# Sheet2.net
KiCad netlist of a schematic drawn in Altium Designer
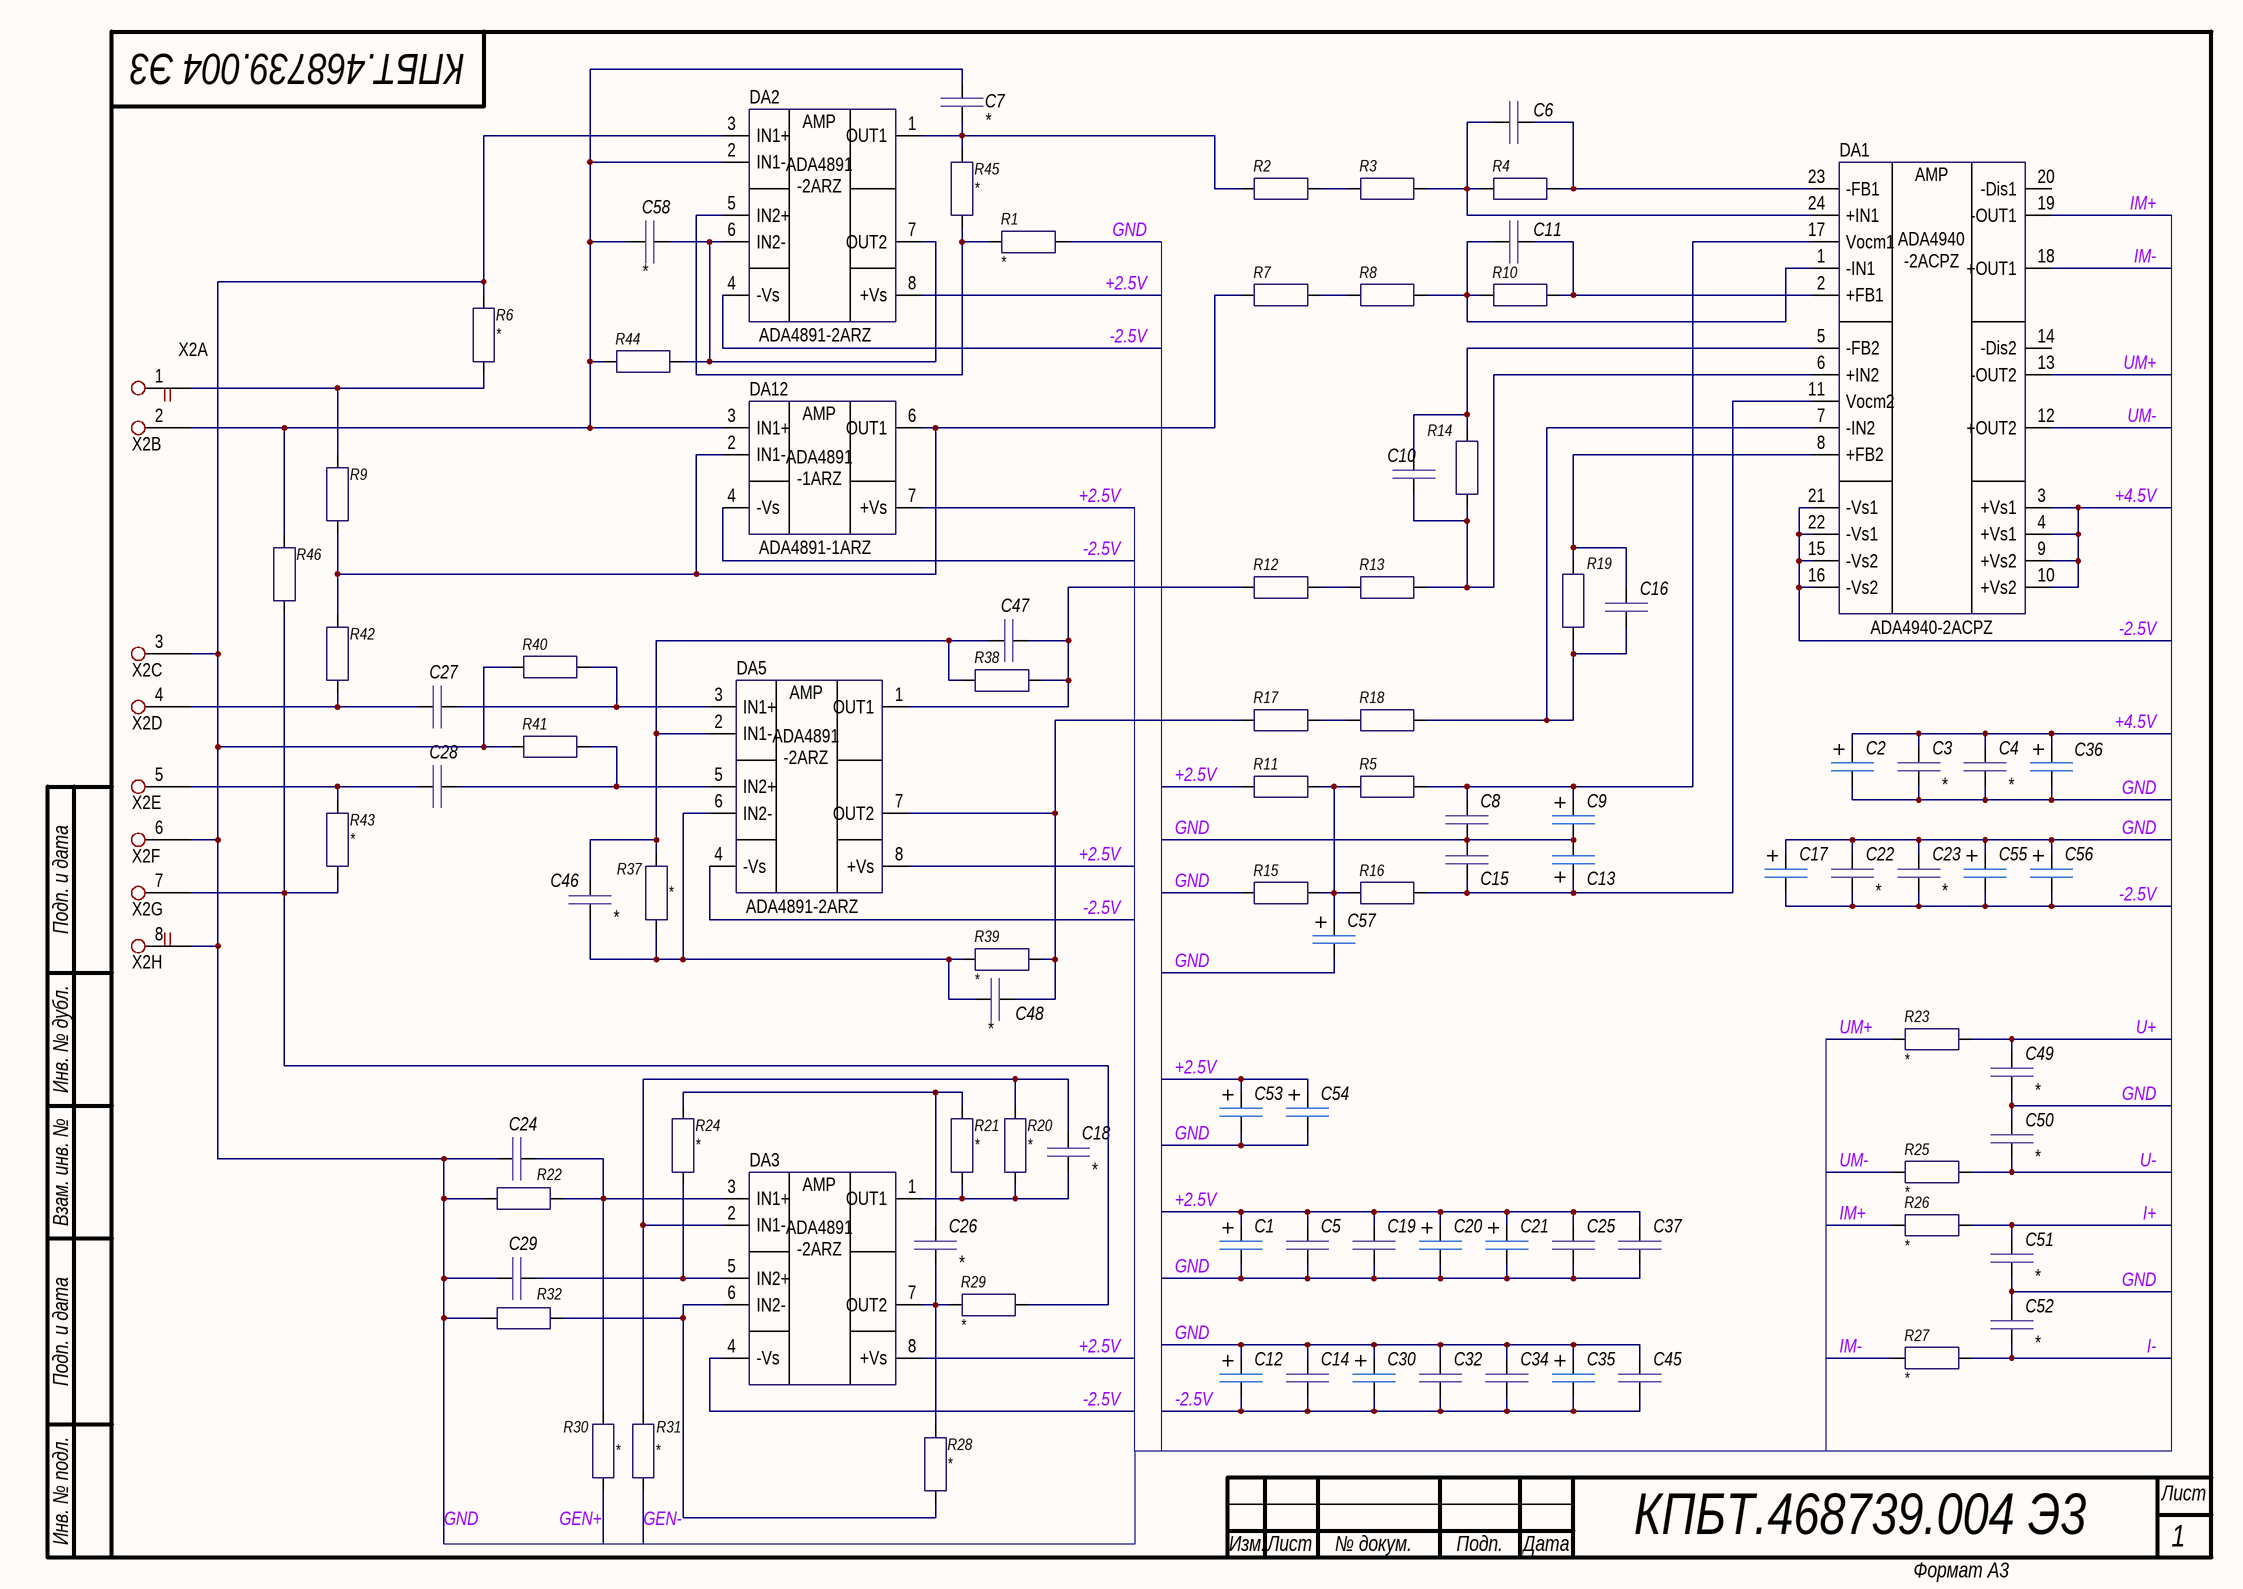
[diagram p0: Sheet2.SchDoc]

(export (version "E")
  (design (tool "Eeschema 10.0.6"))
  (components
    (comp (ref "C1")
      (value "~")
      (footprint "CAPT: tepy B")
      (fields (field (name "PART NUMBER") "CAPT: tepy B"))
      (libsource (lib "LibDb") (part "CAPT{colon} tepy B"))
    )
    (comp (ref "C2")
      (value "~")
      (footprint "CAPT: tepy B")
      (fields (field (name "PART NUMBER") "CAPT: tepy B"))
      (libsource (lib "LibDb") (part "CAPT{colon} tepy B"))
    )
    (comp (ref "C3")
      (value "*")
      (footprint "CAP:0805")
      (fields (field (name "PART NUMBER") "Capacitor 0805"))
      (libsource (lib "LibDb") (part "CAP{colon}0805"))
    )
    (comp (ref "C4")
      (value "*")
      (footprint "CAP:0805")
      (fields (field (name "PART NUMBER") "Capacitor 0805"))
      (libsource (lib "LibDb") (part "CAP{colon}0805"))
    )
    (comp (ref "C5")
      (value "*")
      (footprint "CAP:0805")
      (fields (field (name "PART NUMBER") "Capacitor 0805"))
      (libsource (lib "LibDb") (part "CAP{colon}0805"))
    )
    (comp (ref "C6")
      (value "*")
      (footprint "CAP:0805")
      (fields (field (name "PART NUMBER") "Capacitor 0805"))
      (libsource (lib "LibDb") (part "CAP{colon}0805"))
    )
    (comp (ref "C7")
      (value "*")
      (footprint "CAP:0805")
      (fields (field (name "PART NUMBER") "Capacitor 0805"))
      (libsource (lib "LibDb") (part "CAP{colon}0805"))
    )
    (comp (ref "C8")
      (value "*")
      (footprint "CAP:0805")
      (fields (field (name "PART NUMBER") "Capacitor 0805"))
      (libsource (lib "LibDb") (part "CAP{colon}0805"))
    )
    (comp (ref "C9")
      (value "~")
      (footprint "CAPT: tepy B")
      (fields (field (name "PART NUMBER") "CAPT: tepy B"))
      (libsource (lib "LibDb") (part "CAPT{colon} tepy B"))
    )
    (comp (ref "C10")
      (value "*")
      (footprint "CAP:0805")
      (fields (field (name "PART NUMBER") "Capacitor 0805"))
      (libsource (lib "LibDb") (part "CAP{colon}0805"))
    )
    (comp (ref "C11")
      (value "*")
      (footprint "CAP:0805")
      (fields (field (name "PART NUMBER") "Capacitor 0805"))
      (libsource (lib "LibDb") (part "CAP{colon}0805"))
    )
    (comp (ref "C12")
      (value "~")
      (footprint "CAPT: tepy B")
      (fields (field (name "PART NUMBER") "CAPT: tepy B"))
      (libsource (lib "LibDb") (part "CAPT{colon} tepy B"))
    )
    (comp (ref "C13")
      (value "~")
      (footprint "CAPT: tepy B")
      (fields (field (name "PART NUMBER") "CAPT: tepy B"))
      (libsource (lib "LibDb") (part "CAPT{colon} tepy B"))
    )
    (comp (ref "C14")
      (value "*")
      (footprint "CAP:0805")
      (fields (field (name "PART NUMBER") "Capacitor 0805"))
      (libsource (lib "LibDb") (part "CAP{colon}0805"))
    )
    (comp (ref "C15")
      (value "*")
      (footprint "CAP:0805")
      (fields (field (name "PART NUMBER") "Capacitor 0805"))
      (libsource (lib "LibDb") (part "CAP{colon}0805"))
    )
    (comp (ref "C16")
      (value "*")
      (footprint "CAP:0805")
      (fields (field (name "PART NUMBER") "Capacitor 0805"))
      (libsource (lib "LibDb") (part "CAP{colon}0805"))
    )
    (comp (ref "C17")
      (value "~")
      (footprint "CAPT: tepy B")
      (fields (field (name "PART NUMBER") "CAPT: tepy B"))
      (libsource (lib "LibDb") (part "CAPT{colon} tepy B"))
    )
    (comp (ref "C18")
      (value "*")
      (footprint "CAP:0805")
      (fields (field (name "PART NUMBER") "Capacitor 0805"))
      (libsource (lib "LibDb") (part "CAP{colon}0805"))
    )
    (comp (ref "C19")
      (value "*")
      (footprint "CAP:0805")
      (fields (field (name "PART NUMBER") "Capacitor 0805"))
      (libsource (lib "LibDb") (part "CAP{colon}0805"))
    )
    (comp (ref "C20")
      (value "~")
      (footprint "CAPT: tepy B")
      (fields (field (name "PART NUMBER") "CAPT: tepy B"))
      (libsource (lib "LibDb") (part "CAPT{colon} tepy B"))
    )
    (comp (ref "C21")
      (value "~")
      (footprint "CAPT: tepy B")
      (fields (field (name "PART NUMBER") "CAPT: tepy B"))
      (libsource (lib "LibDb") (part "CAPT{colon} tepy B"))
    )
    (comp (ref "C22")
      (value "*")
      (footprint "CAP:0805")
      (fields (field (name "PART NUMBER") "Capacitor 0805"))
      (libsource (lib "LibDb") (part "CAP{colon}0805"))
    )
    (comp (ref "C23")
      (value "*")
      (footprint "CAP:0805")
      (fields (field (name "PART NUMBER") "Capacitor 0805"))
      (libsource (lib "LibDb") (part "CAP{colon}0805"))
    )
    (comp (ref "C24")
      (value "*")
      (footprint "CAP:0805")
      (fields (field (name "PART NUMBER") "Capacitor 0805"))
      (libsource (lib "LibDb") (part "CAP{colon}0805"))
    )
    (comp (ref "C25")
      (value "*")
      (footprint "CAP:0805")
      (fields (field (name "PART NUMBER") "Capacitor 0805"))
      (libsource (lib "LibDb") (part "CAP{colon}0805"))
    )
    (comp (ref "C26")
      (value "*")
      (footprint "CAP:0805")
      (fields (field (name "PART NUMBER") "Capacitor 0805"))
      (libsource (lib "LibDb") (part "CAP{colon}0805"))
    )
    (comp (ref "C27")
      (value "*")
      (footprint "CAP:0805")
      (fields (field (name "PART NUMBER") "Capacitor 0805"))
      (libsource (lib "LibDb") (part "CAP{colon}0805"))
    )
    (comp (ref "C28")
      (value "*")
      (footprint "CAP:0805")
      (fields (field (name "PART NUMBER") "Capacitor 0805"))
      (libsource (lib "LibDb") (part "CAP{colon}0805"))
    )
    (comp (ref "C29")
      (value "*")
      (footprint "CAP:0805")
      (fields (field (name "PART NUMBER") "Capacitor 0805"))
      (libsource (lib "LibDb") (part "CAP{colon}0805"))
    )
    (comp (ref "C30")
      (value "~")
      (footprint "CAPT: tepy B")
      (fields (field (name "PART NUMBER") "CAPT: tepy B"))
      (libsource (lib "LibDb") (part "CAPT{colon} tepy B"))
    )
    (comp (ref "C32")
      (value "*")
      (footprint "CAP:0805")
      (fields (field (name "PART NUMBER") "Capacitor 0805"))
      (libsource (lib "LibDb") (part "CAP{colon}0805"))
    )
    (comp (ref "C34")
      (value "*")
      (footprint "CAP:0805")
      (fields (field (name "PART NUMBER") "Capacitor 0805"))
      (libsource (lib "LibDb") (part "CAP{colon}0805"))
    )
    (comp (ref "C35")
      (value "~")
      (footprint "CAPT: tepy B")
      (fields (field (name "PART NUMBER") "CAPT: tepy B"))
      (libsource (lib "LibDb") (part "CAPT{colon} tepy B"))
    )
    (comp (ref "C36")
      (value "~")
      (footprint "CAPT: tepy B")
      (fields (field (name "PART NUMBER") "CAPT: tepy B"))
      (libsource (lib "LibDb") (part "CAPT{colon} tepy B"))
    )
    (comp (ref "C37")
      (value "*")
      (footprint "CAP:0805")
      (fields (field (name "PART NUMBER") "Capacitor 0805"))
      (libsource (lib "LibDb") (part "CAP{colon}0805"))
    )
    (comp (ref "C45")
      (value "*")
      (footprint "CAP:0805")
      (fields (field (name "PART NUMBER") "Capacitor 0805"))
      (libsource (lib "LibDb") (part "CAP{colon}0805"))
    )
    (comp (ref "C46")
      (value "*")
      (footprint "CAP:0805")
      (fields (field (name "PART NUMBER") "Capacitor 0805"))
      (libsource (lib "LibDb") (part "CAP{colon}0805"))
    )
    (comp (ref "C47")
      (value "*")
      (footprint "CAP:0805")
      (fields (field (name "PART NUMBER") "Capacitor 0805"))
      (libsource (lib "LibDb") (part "CAP{colon}0805"))
    )
    (comp (ref "C48")
      (value "*")
      (footprint "CAP:0805")
      (fields (field (name "PART NUMBER") "Capacitor 0805"))
      (libsource (lib "LibDb") (part "CAP{colon}0805"))
    )
    (comp (ref "C49")
      (value "*")
      (footprint "CAP:0805")
      (fields (field (name "PART NUMBER") "Capacitor 0805"))
      (libsource (lib "LibDb") (part "CAP{colon}0805"))
    )
    (comp (ref "C50")
      (value "*")
      (footprint "CAP:0805")
      (fields (field (name "PART NUMBER") "Capacitor 0805"))
      (libsource (lib "LibDb") (part "CAP{colon}0805"))
    )
    (comp (ref "C51")
      (value "*")
      (footprint "CAP:0805")
      (fields (field (name "PART NUMBER") "Capacitor 0805"))
      (libsource (lib "LibDb") (part "CAP{colon}0805"))
    )
    (comp (ref "C52")
      (value "*")
      (footprint "CAP:0805")
      (fields (field (name "PART NUMBER") "Capacitor 0805"))
      (libsource (lib "LibDb") (part "CAP{colon}0805"))
    )
    (comp (ref "C53")
      (value "~")
      (footprint "CAPT: tepy B")
      (fields (field (name "PART NUMBER") "CAPT: tepy B"))
      (libsource (lib "LibDb") (part "CAPT{colon} tepy B"))
    )
    (comp (ref "C54")
      (value "~")
      (footprint "CAPT: tepy B")
      (fields (field (name "PART NUMBER") "CAPT: tepy B"))
      (libsource (lib "LibDb") (part "CAPT{colon} tepy B"))
    )
    (comp (ref "C55")
      (value "~")
      (footprint "CAPT: tepy B")
      (fields (field (name "PART NUMBER") "CAPT: tepy B"))
      (libsource (lib "LibDb") (part "CAPT{colon} tepy B"))
    )
    (comp (ref "C56")
      (value "~")
      (footprint "CAPT: tepy B")
      (fields (field (name "PART NUMBER") "CAPT: tepy B"))
      (libsource (lib "LibDb") (part "CAPT{colon} tepy B"))
    )
    (comp (ref "C57")
      (value "~")
      (footprint "CAPT: tepy B")
      (fields (field (name "PART NUMBER") "CAPT: tepy B"))
      (libsource (lib "LibDb") (part "CAPT{colon} tepy B"))
    )
    (comp (ref "C58")
      (value "*")
      (footprint "CAP:0805")
      (fields (field (name "PART NUMBER") "Capacitor 0805"))
      (libsource (lib "LibDb") (part "CAP{colon}0805"))
    )
    (comp (ref "DA1")
      (value "ADA4940-2ACPZ")
      (footprint "LFCSP-24")
      (libsource (lib "LibDb") (part "ADA4940-2ACPZ"))
    )
    (comp (ref "DA2")
      (value "ADA4891-2ARZ")
      (footprint "SOIC-8")
      (libsource (lib "LibDb") (part "ADA4891-2ARZ"))
    )
    (comp (ref "DA3")
      (value "ADA4891-2ARZ")
      (footprint "SOIC-8")
      (libsource (lib "LibDb") (part "ADA4891-2ARZ"))
    )
    (comp (ref "DA5")
      (value "ADA4891-2ARZ")
      (footprint "SOIC-8")
      (libsource (lib "LibDb") (part "ADA4891-2ARZ"))
    )
    (comp (ref "DA12")
      (value "ADA4891-1ARZ")
      (footprint "SOIC-8")
      (libsource (lib "LibDb") (part "ADA4891-1ARZ"))
    )
    (comp (ref "R1")
      (value "*")
      (footprint "RES:0805")
      (fields (field (name "PART NUMBER") "Resistor 0805"))
      (libsource (lib "LibDb") (part "RES{colon}0805"))
    )
    (comp (ref "R2")
      (value "*")
      (footprint "RES:0805")
      (fields (field (name "PART NUMBER") "Resistor 0805"))
      (libsource (lib "LibDb") (part "RES{colon}0805"))
    )
    (comp (ref "R3")
      (value "*")
      (footprint "RES:0805")
      (fields (field (name "PART NUMBER") "Resistor 0805"))
      (libsource (lib "LibDb") (part "RES{colon}0805"))
    )
    (comp (ref "R4")
      (value "*")
      (footprint "RES:0805")
      (fields (field (name "PART NUMBER") "Resistor 0805"))
      (libsource (lib "LibDb") (part "RES{colon}0805"))
    )
    (comp (ref "R5")
      (value "*")
      (footprint "RES:0805")
      (fields (field (name "PART NUMBER") "Resistor 0805"))
      (libsource (lib "LibDb") (part "RES{colon}0805"))
    )
    (comp (ref "R6")
      (value "*")
      (footprint "RES:0805")
      (fields (field (name "PART NUMBER") "Resistor 0805"))
      (libsource (lib "LibDb") (part "RES{colon}0805"))
    )
    (comp (ref "R7")
      (value "*")
      (footprint "RES:0805")
      (fields (field (name "PART NUMBER") "Resistor 0805"))
      (libsource (lib "LibDb") (part "RES{colon}0805"))
    )
    (comp (ref "R8")
      (value "*")
      (footprint "RES:0805")
      (fields (field (name "PART NUMBER") "Resistor 0805"))
      (libsource (lib "LibDb") (part "RES{colon}0805"))
    )
    (comp (ref "R9")
      (value "*")
      (footprint "RES:0805")
      (fields (field (name "PART NUMBER") "Resistor 0805"))
      (libsource (lib "LibDb") (part "RES{colon}0805"))
    )
    (comp (ref "R10")
      (value "*")
      (footprint "RES:0805")
      (fields (field (name "PART NUMBER") "Resistor 0805"))
      (libsource (lib "LibDb") (part "RES{colon}0805"))
    )
    (comp (ref "R11")
      (value "*")
      (footprint "RES:0805")
      (fields (field (name "PART NUMBER") "Resistor 0805"))
      (libsource (lib "LibDb") (part "RES{colon}0805"))
    )
    (comp (ref "R12")
      (value "*")
      (footprint "RES:0805")
      (fields (field (name "PART NUMBER") "Resistor 0805"))
      (libsource (lib "LibDb") (part "RES{colon}0805"))
    )
    (comp (ref "R13")
      (value "*")
      (footprint "RES:0805")
      (fields (field (name "PART NUMBER") "Resistor 0805"))
      (libsource (lib "LibDb") (part "RES{colon}0805"))
    )
    (comp (ref "R14")
      (value "*")
      (footprint "RES:0805")
      (fields (field (name "PART NUMBER") "Resistor 0805"))
      (libsource (lib "LibDb") (part "RES{colon}0805"))
    )
    (comp (ref "R15")
      (value "*")
      (footprint "RES:0805")
      (fields (field (name "PART NUMBER") "Resistor 0805"))
      (libsource (lib "LibDb") (part "RES{colon}0805"))
    )
    (comp (ref "R16")
      (value "*")
      (footprint "RES:0805")
      (fields (field (name "PART NUMBER") "Resistor 0805"))
      (libsource (lib "LibDb") (part "RES{colon}0805"))
    )
    (comp (ref "R17")
      (value "*")
      (footprint "RES:0805")
      (fields (field (name "PART NUMBER") "Resistor 0805"))
      (libsource (lib "LibDb") (part "RES{colon}0805"))
    )
    (comp (ref "R18")
      (value "*")
      (footprint "RES:0805")
      (fields (field (name "PART NUMBER") "Resistor 0805"))
      (libsource (lib "LibDb") (part "RES{colon}0805"))
    )
    (comp (ref "R19")
      (value "*")
      (footprint "RES:0805")
      (fields (field (name "PART NUMBER") "Resistor 0805"))
      (libsource (lib "LibDb") (part "RES{colon}0805"))
    )
    (comp (ref "R20")
      (value "*")
      (footprint "RES:0805")
      (fields (field (name "PART NUMBER") "Resistor 0805"))
      (libsource (lib "LibDb") (part "RES{colon}0805"))
    )
    (comp (ref "R21")
      (value "*")
      (footprint "RES:0805")
      (fields (field (name "PART NUMBER") "Resistor 0805"))
      (libsource (lib "LibDb") (part "RES{colon}0805"))
    )
    (comp (ref "R22")
      (value "*")
      (footprint "RES:0805")
      (fields (field (name "PART NUMBER") "Resistor 0805"))
      (libsource (lib "LibDb") (part "RES{colon}0805"))
    )
    (comp (ref "R23")
      (value "*")
      (footprint "RES:0805")
      (fields (field (name "PART NUMBER") "Resistor 0805"))
      (libsource (lib "LibDb") (part "RES{colon}0805"))
    )
    (comp (ref "R24")
      (value "*")
      (footprint "RES:0805")
      (fields (field (name "PART NUMBER") "Resistor 0805"))
      (libsource (lib "LibDb") (part "RES{colon}0805"))
    )
    (comp (ref "R25")
      (value "*")
      (footprint "RES:0805")
      (fields (field (name "PART NUMBER") "Resistor 0805"))
      (libsource (lib "LibDb") (part "RES{colon}0805"))
    )
    (comp (ref "R26")
      (value "*")
      (footprint "RES:0805")
      (fields (field (name "PART NUMBER") "Resistor 0805"))
      (libsource (lib "LibDb") (part "RES{colon}0805"))
    )
    (comp (ref "R27")
      (value "*")
      (footprint "RES:0805")
      (fields (field (name "PART NUMBER") "Resistor 0805"))
      (libsource (lib "LibDb") (part "RES{colon}0805"))
    )
    (comp (ref "R28")
      (value "*")
      (footprint "RES:0805")
      (fields (field (name "PART NUMBER") "Resistor 0805"))
      (libsource (lib "LibDb") (part "RES{colon}0805"))
    )
    (comp (ref "R29")
      (value "*")
      (footprint "RES:0805")
      (fields (field (name "PART NUMBER") "Resistor 0805"))
      (libsource (lib "LibDb") (part "RES{colon}0805"))
    )
    (comp (ref "R30")
      (value "*")
      (footprint "RES:0805")
      (fields (field (name "PART NUMBER") "Resistor 0805"))
      (libsource (lib "LibDb") (part "RES{colon}0805"))
    )
    (comp (ref "R31")
      (value "*")
      (footprint "RES:0805")
      (fields (field (name "PART NUMBER") "Resistor 0805"))
      (libsource (lib "LibDb") (part "RES{colon}0805"))
    )
    (comp (ref "R32")
      (value "*")
      (footprint "RES:0805")
      (fields (field (name "PART NUMBER") "Resistor 0805"))
      (libsource (lib "LibDb") (part "RES{colon}0805"))
    )
    (comp (ref "R37")
      (value "*")
      (footprint "RES:0805")
      (fields (field (name "PART NUMBER") "Resistor 0805"))
      (libsource (lib "LibDb") (part "RES{colon}0805"))
    )
    (comp (ref "R38")
      (value "*")
      (footprint "RES:0805")
      (fields (field (name "PART NUMBER") "Resistor 0805"))
      (libsource (lib "LibDb") (part "RES{colon}0805"))
    )
    (comp (ref "R39")
      (value "*")
      (footprint "RES:0805")
      (fields (field (name "PART NUMBER") "Resistor 0805"))
      (libsource (lib "LibDb") (part "RES{colon}0805"))
    )
    (comp (ref "R40")
      (value "*")
      (footprint "RES:0805")
      (fields (field (name "PART NUMBER") "Resistor 0805"))
      (libsource (lib "LibDb") (part "RES{colon}0805"))
    )
    (comp (ref "R41")
      (value "*")
      (footprint "RES:0805")
      (fields (field (name "PART NUMBER") "Resistor 0805"))
      (libsource (lib "LibDb") (part "RES{colon}0805"))
    )
    (comp (ref "R42")
      (value "*")
      (footprint "RES:0805")
      (fields (field (name "PART NUMBER") "Resistor 0805"))
      (libsource (lib "LibDb") (part "RES{colon}0805"))
    )
    (comp (ref "R43")
      (value "*")
      (footprint "RES:0805")
      (fields (field (name "PART NUMBER") "Resistor 0805"))
      (libsource (lib "LibDb") (part "RES{colon}0805"))
    )
    (comp (ref "R44")
      (value "*")
      (footprint "RES:0805")
      (fields (field (name "PART NUMBER") "Resistor 0805"))
      (libsource (lib "LibDb") (part "RES{colon}0805"))
    )
    (comp (ref "R45")
      (value "*")
      (footprint "RES:0805")
      (fields (field (name "PART NUMBER") "Resistor 0805"))
      (libsource (lib "LibDb") (part "RES{colon}0805"))
    )
    (comp (ref "R46")
      (value "~")
      (footprint "RES:0805")
      (fields (field (name "PART NUMBER") "Resistor 0805"))
      (libsource (lib "LibDb") (part "RES{colon}0805"))
    )
    (comp (ref "X2")
      (value "~")
      (footprint "15EDGVC-3.5-08P-14-00AH")
      (fields (field (name "PART NUMBER") "15EDGVC-3.5-08P-14-00AH_1"))
      (libsource (lib "LibDb") (part "15EDGVC-3.5-08P-14-00AH_1"))
    )
  )
  (nets
    (net (code "1") (name "/+2.5V") (class "Default")
      (node (ref "C1") (pin "2") (pintype "passive"))
      (node (ref "C19") (pin "2") (pintype "passive"))
      (node (ref "C20") (pin "2") (pintype "passive"))
      (node (ref "C21") (pin "2") (pintype "passive"))
      (node (ref "C25") (pin "2") (pintype "passive"))
      (node (ref "C37") (pin "2") (pintype "passive"))
      (node (ref "C5") (pin "2") (pintype "passive"))
      (node (ref "C53") (pin "2") (pintype "passive"))
      (node (ref "C54") (pin "2") (pintype "passive"))
      (node (ref "DA12") (pin "7") (pinfunction "+Vs_7") (pintype "passive"))
      (node (ref "DA2") (pin "8") (pinfunction "+Vs_8") (pintype "passive"))
      (node (ref "DA3") (pin "8") (pinfunction "+Vs_8") (pintype "passive"))
      (node (ref "DA5") (pin "8") (pinfunction "+Vs_8") (pintype "passive"))
      (node (ref "R11") (pin "2") (pintype "passive"))
    )
    (net (code "2") (name "/+4.5V") (class "Default")
      (node (ref "C2") (pin "2") (pintype "passive"))
      (node (ref "C3") (pin "2") (pintype "passive"))
      (node (ref "C36") (pin "2") (pintype "passive"))
      (node (ref "C4") (pin "2") (pintype "passive"))
      (node (ref "DA1") (pin "10") (pinfunction "+Vs2_10") (pintype "passive"))
      (node (ref "DA1") (pin "3") (pinfunction "+Vs1_3") (pintype "passive"))
      (node (ref "DA1") (pin "4") (pinfunction "+Vs1_4") (pintype "passive"))
      (node (ref "DA1") (pin "9") (pinfunction "+Vs2_9") (pintype "passive"))
    )
    (net (code "3") (name "/-2.5V") (class "Default")
      (node (ref "C12") (pin "1") (pintype "passive"))
      (node (ref "C14") (pin "1") (pintype "passive"))
      (node (ref "C17") (pin "1") (pintype "passive"))
      (node (ref "C22") (pin "1") (pintype "passive"))
      (node (ref "C23") (pin "1") (pintype "passive"))
      (node (ref "C30") (pin "1") (pintype "passive"))
      (node (ref "C32") (pin "1") (pintype "passive"))
      (node (ref "C34") (pin "1") (pintype "passive"))
      (node (ref "C35") (pin "1") (pintype "passive"))
      (node (ref "C45") (pin "1") (pintype "passive"))
      (node (ref "C55") (pin "1") (pintype "passive"))
      (node (ref "C56") (pin "1") (pintype "passive"))
      (node (ref "DA1") (pin "15") (pinfunction "-Vs2_15") (pintype "passive"))
      (node (ref "DA1") (pin "16") (pinfunction "-Vs2_16") (pintype "passive"))
      (node (ref "DA1") (pin "21") (pinfunction "-Vs1_21") (pintype "passive"))
      (node (ref "DA1") (pin "22") (pinfunction "-Vs1_22") (pintype "passive"))
      (node (ref "DA12") (pin "4") (pinfunction "-Vs_4") (pintype "passive"))
      (node (ref "DA2") (pin "4") (pinfunction "-Vs_4") (pintype "passive"))
      (node (ref "DA3") (pin "4") (pinfunction "-Vs_4") (pintype "passive"))
      (node (ref "DA5") (pin "4") (pinfunction "-Vs_4") (pintype "passive"))
    )
    (net (code "4") (name "/GEN+") (class "Default") (node (ref "R30") (pin "1") (pintype "passive")))
    (net (code "5") (name "/GEN-") (class "Default") (node (ref "R31") (pin "1") (pintype "passive")))
    (net (code "6") (name "/GND") (class "Default")
      (node (ref "C1") (pin "1") (pintype "passive"))
      (node (ref "C12") (pin "2") (pintype "passive"))
      (node (ref "C13") (pin "1") (pintype "passive"))
      (node (ref "C14") (pin "2") (pintype "passive"))
      (node (ref "C15") (pin "2") (pintype "passive"))
      (node (ref "C17") (pin "2") (pintype "passive"))
      (node (ref "C19") (pin "1") (pintype "passive"))
      (node (ref "C2") (pin "1") (pintype "passive"))
      (node (ref "C20") (pin "1") (pintype "passive"))
      (node (ref "C21") (pin "1") (pintype "passive"))
      (node (ref "C22") (pin "2") (pintype "passive"))
      (node (ref "C23") (pin "2") (pintype "passive"))
      (node (ref "C24") (pin "2") (pintype "passive"))
      (node (ref "C25") (pin "1") (pintype "passive"))
      (node (ref "C29") (pin "2") (pintype "passive"))
      (node (ref "C3") (pin "1") (pintype "passive"))
      (node (ref "C30") (pin "2") (pintype "passive"))
      (node (ref "C32") (pin "2") (pintype "passive"))
      (node (ref "C34") (pin "2") (pintype "passive"))
      (node (ref "C35") (pin "2") (pintype "passive"))
      (node (ref "C36") (pin "1") (pintype "passive"))
      (node (ref "C37") (pin "1") (pintype "passive"))
      (node (ref "C4") (pin "1") (pintype "passive"))
      (node (ref "C45") (pin "2") (pintype "passive"))
      (node (ref "C49") (pin "1") (pintype "passive"))
      (node (ref "C5") (pin "1") (pintype "passive"))
      (node (ref "C50") (pin "2") (pintype "passive"))
      (node (ref "C51") (pin "1") (pintype "passive"))
      (node (ref "C52") (pin "2") (pintype "passive"))
      (node (ref "C53") (pin "1") (pintype "passive"))
      (node (ref "C54") (pin "1") (pintype "passive"))
      (node (ref "C55") (pin "2") (pintype "passive"))
      (node (ref "C56") (pin "2") (pintype "passive"))
      (node (ref "C57") (pin "1") (pintype "passive"))
      (node (ref "C8") (pin "1") (pintype "passive"))
      (node (ref "C9") (pin "1") (pintype "passive"))
      (node (ref "DA2") (pin "3") (pinfunction "IN1+_3") (pintype "passive"))
      (node (ref "R1") (pin "1") (pintype "passive"))
      (node (ref "R15") (pin "2") (pintype "passive"))
      (node (ref "R22") (pin "2") (pintype "passive"))
      (node (ref "R32") (pin "2") (pintype "passive"))
      (node (ref "R40") (pin "2") (pintype "passive"))
      (node (ref "R41") (pin "2") (pintype "passive"))
      (node (ref "R6") (pin "2") (pintype "passive"))
      (node (ref "X2") (pin "3") (pintype "passive"))
      (node (ref "X2") (pin "6") (pintype "passive"))
      (node (ref "X2") (pin "8") (pintype "passive"))
    )
    (net (code "7") (name "/I+") (class "Default")
      (node (ref "C51") (pin "2") (pintype "passive"))
      (node (ref "R26") (pin "1") (pintype "passive"))
    )
    (net (code "8") (name "/I-") (class "Default")
      (node (ref "C52") (pin "1") (pintype "passive"))
      (node (ref "R27") (pin "1") (pintype "passive"))
    )
    (net (code "9") (name "/IM+") (class "Default")
      (node (ref "DA1") (pin "19") (pinfunction "-OUT1_19") (pintype "passive"))
      (node (ref "R26") (pin "2") (pintype "passive"))
    )
    (net (code "10") (name "/IM-") (class "Default")
      (node (ref "DA1") (pin "18") (pinfunction "+OUT1_18") (pintype "passive"))
      (node (ref "R27") (pin "2") (pintype "passive"))
    )
    (net (code "11") (name "/U+") (class "Default")
      (node (ref "C49") (pin "2") (pintype "passive"))
      (node (ref "R23") (pin "1") (pintype "passive"))
    )
    (net (code "12") (name "/U-") (class "Default")
      (node (ref "C50") (pin "1") (pintype "passive"))
      (node (ref "R25") (pin "1") (pintype "passive"))
    )
    (net (code "13") (name "/UM+") (class "Default")
      (node (ref "DA1") (pin "13") (pinfunction "-OUT2_13") (pintype "passive"))
      (node (ref "R23") (pin "2") (pintype "passive"))
    )
    (net (code "14") (name "/UM-") (class "Default")
      (node (ref "DA1") (pin "12") (pinfunction "+OUT2_12") (pintype "passive"))
      (node (ref "R25") (pin "2") (pintype "passive"))
    )
    (net (code "15") (name "Net-(C26-Pad2)") (class "Default")
      (node (ref "C26") (pin "2") (pintype "passive"))
      (node (ref "R21") (pin "2") (pintype "passive"))
      (node (ref "R24") (pin "2") (pintype "passive"))
    )
    (net (code "16") (name "Net-(C27-Pad2)") (class "Default")
      (node (ref "C27") (pin "2") (pintype "passive"))
      (node (ref "R42") (pin "1") (pintype "passive"))
      (node (ref "X2") (pin "4") (pintype "passive"))
    )
    (net (code "17") (name "Net-(C28-Pad2)") (class "Default")
      (node (ref "C28") (pin "2") (pintype "passive"))
      (node (ref "R43") (pin "2") (pintype "passive"))
      (node (ref "X2") (pin "5") (pintype "passive"))
    )
    (net (code "18") (name "Net-(C57-Pad2)") (class "Default")
      (node (ref "C57") (pin "2") (pintype "passive"))
      (node (ref "R11") (pin "1") (pintype "passive"))
      (node (ref "R15") (pin "1") (pintype "passive"))
      (node (ref "R16") (pin "2") (pintype "passive"))
      (node (ref "R5") (pin "2") (pintype "passive"))
    )
    (net (code "19") (name "Net-(DA1-+FB1)") (class "Default")
      (node (ref "C11") (pin "1") (pintype "passive"))
      (node (ref "DA1") (pin "2") (pinfunction "+FB1_2") (pintype "passive"))
      (node (ref "R10") (pin "1") (pintype "passive"))
    )
    (net (code "20") (name "Net-(DA1-+FB2)") (class "Default")
      (node (ref "C16") (pin "2") (pintype "passive"))
      (node (ref "DA1") (pin "8") (pinfunction "+FB2_8") (pintype "passive"))
      (node (ref "R19") (pin "1") (pintype "passive"))
    )
    (net (code "21") (name "Net-(DA1-+IN1)") (class "Default")
      (node (ref "C6") (pin "2") (pintype "passive"))
      (node (ref "DA1") (pin "24") (pinfunction "+IN1_24") (pintype "passive"))
      (node (ref "R3") (pin "1") (pintype "passive"))
      (node (ref "R4") (pin "2") (pintype "passive"))
    )
    (net (code "22") (name "Net-(DA1-+IN2)") (class "Default")
      (node (ref "C10") (pin "2") (pintype "passive"))
      (node (ref "DA1") (pin "6") (pinfunction "+IN2_6") (pintype "passive"))
      (node (ref "R13") (pin "1") (pintype "passive"))
      (node (ref "R14") (pin "2") (pintype "passive"))
    )
    (net (code "23") (name "Net-(DA1--FB1)") (class "Default")
      (node (ref "C6") (pin "1") (pintype "passive"))
      (node (ref "DA1") (pin "23") (pinfunction "-FB1_23") (pintype "passive"))
      (node (ref "R4") (pin "1") (pintype "passive"))
    )
    (net (code "24") (name "Net-(DA1--FB2)") (class "Default")
      (node (ref "C10") (pin "1") (pintype "passive"))
      (node (ref "DA1") (pin "5") (pinfunction "-FB2_5") (pintype "passive"))
      (node (ref "R14") (pin "1") (pintype "passive"))
    )
    (net (code "25") (name "Net-(DA1--IN1)") (class "Default")
      (node (ref "C11") (pin "2") (pintype "passive"))
      (node (ref "DA1") (pin "1") (pinfunction "-IN1_1") (pintype "passive"))
      (node (ref "R10") (pin "2") (pintype "passive"))
      (node (ref "R8") (pin "1") (pintype "passive"))
    )
    (net (code "26") (name "Net-(DA1--IN2)") (class "Default")
      (node (ref "C16") (pin "1") (pintype "passive"))
      (node (ref "DA1") (pin "7") (pinfunction "-IN2_7") (pintype "passive"))
      (node (ref "R18") (pin "1") (pintype "passive"))
      (node (ref "R19") (pin "2") (pintype "passive"))
    )
    (net (code "27") (name "Net-(DA1-Vocm1)") (class "Default")
      (node (ref "C8") (pin "2") (pintype "passive"))
      (node (ref "C9") (pin "2") (pintype "passive"))
      (node (ref "DA1") (pin "17") (pinfunction "Vocm1_17") (pintype "passive"))
      (node (ref "R5") (pin "1") (pintype "passive"))
    )
    (net (code "28") (name "Net-(DA1-Vocm2)") (class "Default")
      (node (ref "C13") (pin "2") (pintype "passive"))
      (node (ref "C15") (pin "1") (pintype "passive"))
      (node (ref "DA1") (pin "11") (pinfunction "Vocm2_11") (pintype "passive"))
      (node (ref "R16") (pin "1") (pintype "passive"))
    )
    (net (code "29") (name "Net-(DA2-IN2+)") (class "Default")
      (node (ref "DA2") (pin "5") (pinfunction "IN2+_5") (pintype "passive"))
      (node (ref "R1") (pin "2") (pintype "passive"))
      (node (ref "R45") (pin "1") (pintype "passive"))
    )
    (net (code "30") (name "Net-(DA2-IN2-)") (class "Default")
      (node (ref "C58") (pin "1") (pintype "passive"))
      (node (ref "DA2") (pin "6") (pinfunction "IN2-_6") (pintype "passive"))
      (node (ref "DA2") (pin "7") (pinfunction "OUT2_7") (pintype "passive"))
      (node (ref "R44") (pin "1") (pintype "passive"))
    )
    (net (code "31") (name "Net-(DA2-OUT1)") (class "Default")
      (node (ref "C7") (pin "1") (pintype "passive"))
      (node (ref "DA2") (pin "1") (pinfunction "OUT1_1") (pintype "passive"))
      (node (ref "R2") (pin "2") (pintype "passive"))
      (node (ref "R45") (pin "2") (pintype "passive"))
    )
    (net (code "32") (name "Net-(DA3-IN1+)") (class "Default")
      (node (ref "C24") (pin "1") (pintype "passive"))
      (node (ref "DA3") (pin "3") (pinfunction "IN1+_3") (pintype "passive"))
      (node (ref "R22") (pin "1") (pintype "passive"))
      (node (ref "R30") (pin "2") (pintype "passive"))
    )
    (net (code "33") (name "Net-(DA3-IN1-)") (class "Default")
      (node (ref "C18") (pin "2") (pintype "passive"))
      (node (ref "DA3") (pin "2") (pinfunction "IN1-_2") (pintype "passive"))
      (node (ref "R20") (pin "2") (pintype "passive"))
      (node (ref "R31") (pin "2") (pintype "passive"))
    )
    (net (code "34") (name "Net-(DA3-IN2+)") (class "Default")
      (node (ref "C29") (pin "1") (pintype "passive"))
      (node (ref "DA3") (pin "5") (pinfunction "IN2+_5") (pintype "passive"))
      (node (ref "R24") (pin "1") (pintype "passive"))
    )
    (net (code "35") (name "Net-(DA3-IN2-)") (class "Default")
      (node (ref "DA3") (pin "6") (pinfunction "IN2-_6") (pintype "passive"))
      (node (ref "R28") (pin "1") (pintype "passive"))
      (node (ref "R32") (pin "1") (pintype "passive"))
    )
    (net (code "36") (name "Net-(DA3-OUT1)") (class "Default")
      (node (ref "C18") (pin "1") (pintype "passive"))
      (node (ref "DA3") (pin "1") (pinfunction "OUT1_1") (pintype "passive"))
      (node (ref "R20") (pin "1") (pintype "passive"))
      (node (ref "R21") (pin "1") (pintype "passive"))
    )
    (net (code "37") (name "Net-(DA3-OUT2)") (class "Default")
      (node (ref "C26") (pin "1") (pintype "passive"))
      (node (ref "DA3") (pin "7") (pinfunction "OUT2_7") (pintype "passive"))
      (node (ref "R28") (pin "2") (pintype "passive"))
      (node (ref "R29") (pin "1") (pintype "passive"))
    )
    (net (code "38") (name "Net-(DA5-IN1+)") (class "Default")
      (node (ref "C27") (pin "1") (pintype "passive"))
      (node (ref "DA5") (pin "3") (pinfunction "IN1+_3") (pintype "passive"))
      (node (ref "R40") (pin "1") (pintype "passive"))
    )
    (net (code "39") (name "Net-(DA5-IN1-)") (class "Default")
      (node (ref "C46") (pin "1") (pintype "passive"))
      (node (ref "C47") (pin "2") (pintype "passive"))
      (node (ref "DA5") (pin "2") (pinfunction "IN1-_2") (pintype "passive"))
      (node (ref "R37") (pin "1") (pintype "passive"))
      (node (ref "R38") (pin "2") (pintype "passive"))
    )
    (net (code "40") (name "Net-(DA5-IN2+)") (class "Default")
      (node (ref "C28") (pin "1") (pintype "passive"))
      (node (ref "DA5") (pin "5") (pinfunction "IN2+_5") (pintype "passive"))
      (node (ref "R41") (pin "1") (pintype "passive"))
    )
    (net (code "41") (name "Net-(DA5-IN2-)") (class "Default")
      (node (ref "C46") (pin "2") (pintype "passive"))
      (node (ref "C48") (pin "1") (pintype "passive"))
      (node (ref "DA5") (pin "6") (pinfunction "IN2-_6") (pintype "passive"))
      (node (ref "R37") (pin "2") (pintype "passive"))
      (node (ref "R39") (pin "1") (pintype "passive"))
    )
    (net (code "42") (name "Net-(DA5-OUT1)") (class "Default")
      (node (ref "C47") (pin "1") (pintype "passive"))
      (node (ref "DA5") (pin "1") (pinfunction "OUT1_1") (pintype "passive"))
      (node (ref "R12") (pin "2") (pintype "passive"))
      (node (ref "R38") (pin "1") (pintype "passive"))
    )
    (net (code "43") (name "Net-(DA5-OUT2)") (class "Default")
      (node (ref "C48") (pin "2") (pintype "passive"))
      (node (ref "DA5") (pin "7") (pinfunction "OUT2_7") (pintype "passive"))
      (node (ref "R17") (pin "2") (pintype "passive"))
      (node (ref "R39") (pin "2") (pintype "passive"))
    )
    (net (code "44") (name "Net-(DA12-IN1+)") (class "Default")
      (node (ref "C58") (pin "2") (pintype "passive"))
      (node (ref "C7") (pin "2") (pintype "passive"))
      (node (ref "DA12") (pin "3") (pinfunction "IN1+_3") (pintype "passive"))
      (node (ref "DA2") (pin "2") (pinfunction "IN1-_2") (pintype "passive"))
      (node (ref "R44") (pin "2") (pintype "passive"))
      (node (ref "R46") (pin "2") (pintype "passive"))
      (node (ref "X2") (pin "2") (pintype "passive"))
    )
    (net (code "45") (name "Net-(DA12-IN1-)") (class "Default")
      (node (ref "DA12") (pin "2") (pinfunction "IN1-_2") (pintype "passive"))
      (node (ref "DA12") (pin "6") (pinfunction "OUT1_6") (pintype "passive"))
      (node (ref "R42") (pin "2") (pintype "passive"))
      (node (ref "R7") (pin "2") (pintype "passive"))
      (node (ref "R9") (pin "1") (pintype "passive"))
    )
    (net (code "46") (name "Net-(R2-Pad1)") (class "Default")
      (node (ref "R2") (pin "1") (pintype "passive"))
      (node (ref "R3") (pin "2") (pintype "passive"))
    )
    (net (code "47") (name "Net-(R6-Pad1)") (class "Default")
      (node (ref "R6") (pin "1") (pintype "passive"))
      (node (ref "R9") (pin "2") (pintype "passive"))
      (node (ref "X2") (pin "1") (pintype "passive"))
    )
    (net (code "48") (name "Net-(R7-Pad1)") (class "Default")
      (node (ref "R7") (pin "1") (pintype "passive"))
      (node (ref "R8") (pin "2") (pintype "passive"))
    )
    (net (code "49") (name "Net-(R12-Pad1)") (class "Default")
      (node (ref "R12") (pin "1") (pintype "passive"))
      (node (ref "R13") (pin "2") (pintype "passive"))
    )
    (net (code "50") (name "Net-(R17-Pad1)") (class "Default")
      (node (ref "R17") (pin "1") (pintype "passive"))
      (node (ref "R18") (pin "2") (pintype "passive"))
    )
    (net (code "51") (name "Net-(R29-Pad2)") (class "Default")
      (node (ref "R29") (pin "2") (pintype "passive"))
      (node (ref "R43") (pin "1") (pintype "passive"))
      (node (ref "R46") (pin "1") (pintype "passive"))
      (node (ref "X2") (pin "7") (pintype "passive"))
    )
    (net (code "52") (name "unconnected-(DA1--Dis1-Pad20)") (class "Default")
      (node (ref "DA1") (pin "20") (pinfunction "-Dis1_20") (pintype "passive"))
    )
    (net (code "53") (name "unconnected-(DA1--Dis2-Pad14)") (class "Default")
      (node (ref "DA1") (pin "14") (pinfunction "-Dis2_14") (pintype "passive"))
    )
  )
)
